# SCH_StorageGuard.net
KiCad netlist of a schematic drawn in EasyEDA
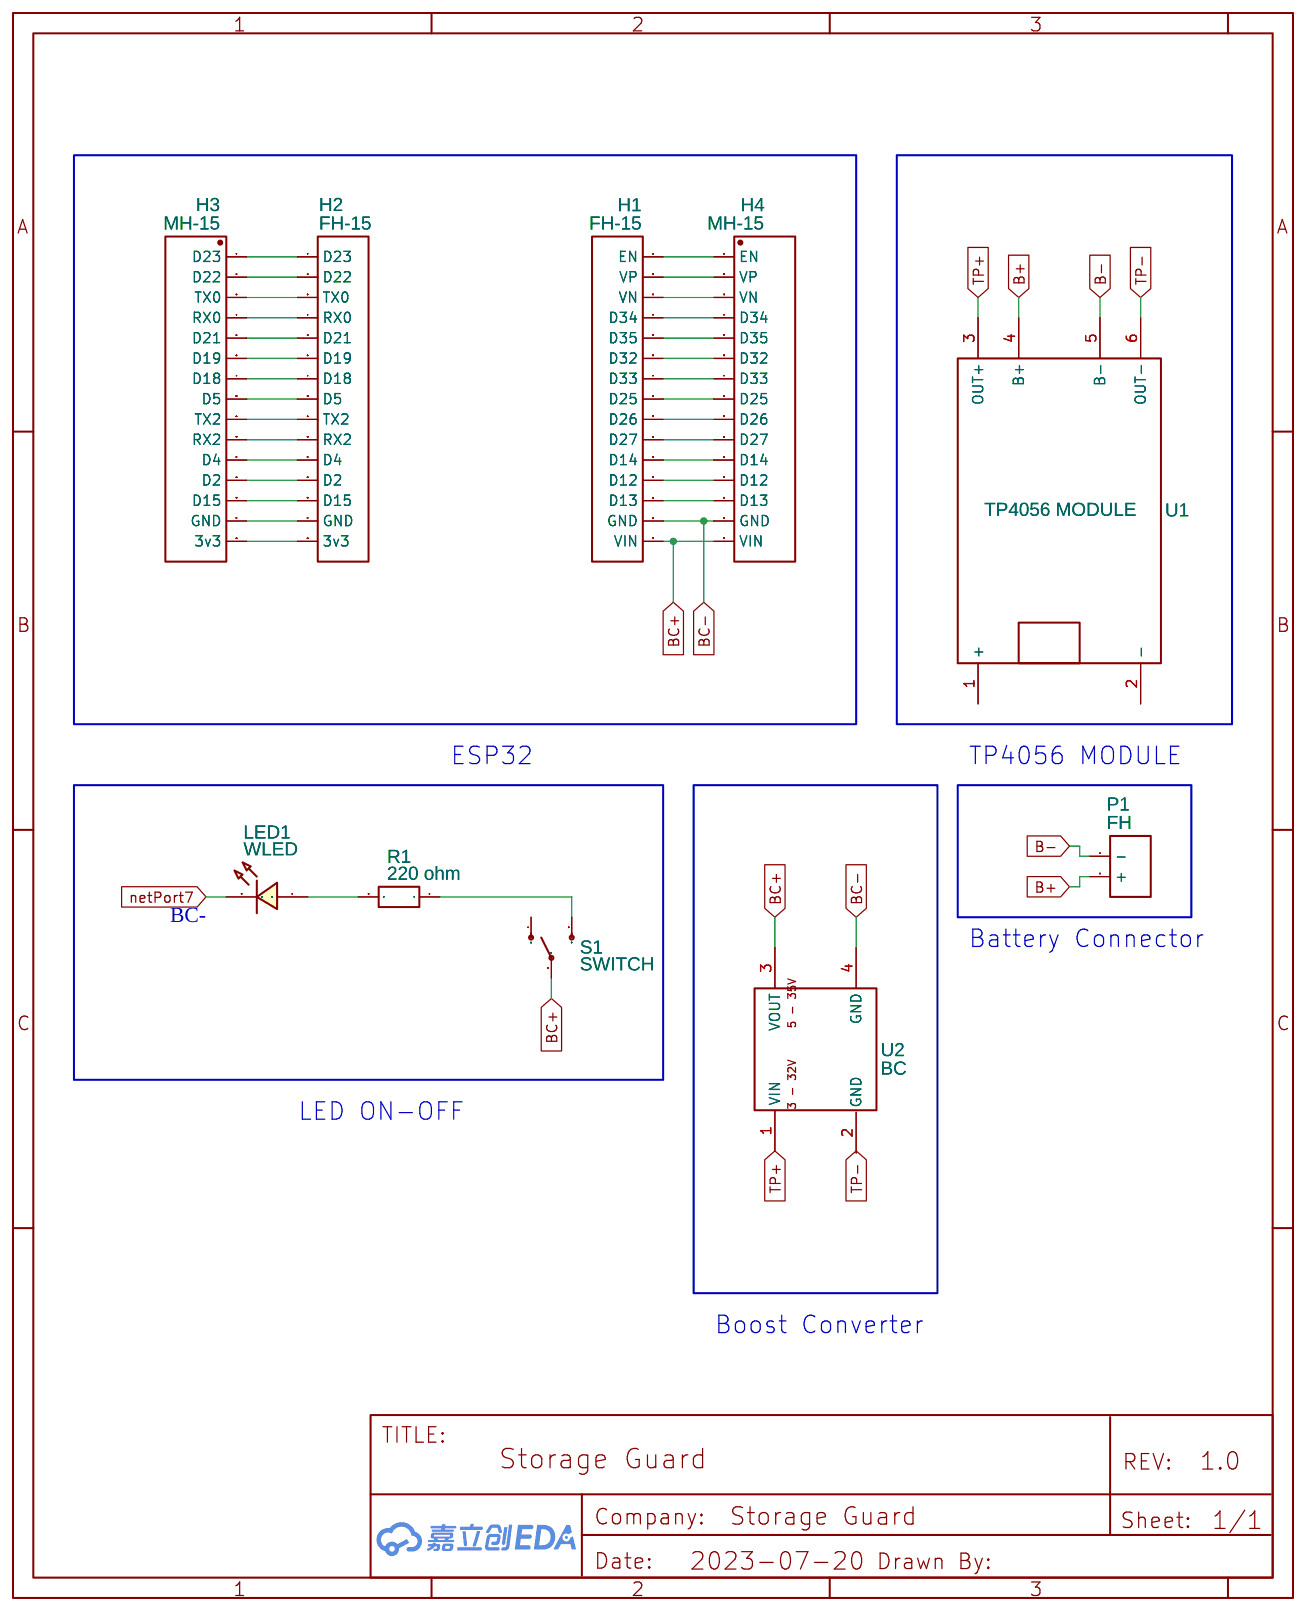
[diagram p0: schematic sheet]

(export (version "E")
  (design (tool "Eeschema 10.0.6"))
  (components
    (comp (ref "H1")
      (value "FH-15")
      (fields
        (field (name "BOM_Manufacturer Part") "B-2200S15P-A120")
        (field (name "BOM_Supplier Part") "C124408")
      )
      (libsource (lib "") (part "Header-Female-2.54_1x15"))
    )
    (comp (ref "H2")
      (value "FH-15")
      (fields
        (field (name "BOM_Manufacturer Part") "B-2200S15P-A120")
        (field (name "BOM_Supplier Part") "C124408")
      )
      (libsource (lib "") (part "Header-Female-2.54_1x15_1"))
    )
    (comp (ref "H3")
      (value "MH-15")
      (fields
        (field (name "BOM_Manufacturer Part") "B-2100S15P-A110")
        (field (name "BOM_Supplier Part") "C124373")
      )
      (libsource (lib "") (part "Header-Male-2.54_1x15"))
    )
    (comp (ref "H4")
      (value "MH-15")
      (fields
        (field (name "BOM_Manufacturer Part") "B-2100S15P-A110")
        (field (name "BOM_Supplier Part") "C124373")
      )
      (libsource (lib "") (part "Header-Male-2.54_1x15_1"))
    )
    (comp (ref "LED1") (value "WLED") (libsource (lib "") (part "LED-TH-5mm_B")))
    (comp (ref "P1")
      (value "FH")
      (fields (field (name "BOM_Manufacturer Part") "2.54-1*2P母") (field (name "BOM_Supplier Part") "C49661"))
      (libsource (lib "") (part "Header-Female-2.54_1x2"))
    )
    (comp (ref "R1")
      (value "220 ohm")
      (fields
        (field (name "BOM_Manufacturer Part") "Resistor_THT:R_Axial_DIN0309_L9.0mm_D3.2mm_P2.54mm_Vertical")
        (field (name "BOM_Supplier Part") "C9900016274")
      )
      (libsource (lib "") (part "RESISTOR_THT{colon}R_AXIAL_DIN0309_L9.0MM_D3.2MM_P2.54MM_VERTICAL"))
    )
    (comp (ref "S1") (value "SWITCH") (libsource (lib "") (part "SWITCH-SPDT-8.5mm")))
    (comp (ref "U1") (value "TP4056 MODULE") (libsource (lib "") (part "TP4056 MODULE")))
    (comp (ref "U2") (value "BC") (libsource (lib "") (part "STEP-UP XL6009E1")))
  )
  (nets
    (net (code "1") (name "B+") (class "Default")
      (node (ref "P1") (pin "2") (pinfunction "+_2") (pintype "input"))
      (node (ref "U1") (pin "4") (pinfunction "B+_4") (pintype "unspecified"))
    )
    (net (code "2") (name "B-") (class "Default")
      (node (ref "P1") (pin "1") (pinfunction "-_1") (pintype "input"))
      (node (ref "U1") (pin "5") (pinfunction "B-_5") (pintype "unspecified"))
    )
    (net (code "3") (name "BC+") (class "Default")
      (node (ref "H1") (pin "15") (pinfunction "VIN_15") (pintype "unspecified"))
      (node (ref "H4") (pin "15") (pinfunction "VIN_15") (pintype "unspecified"))
      (node (ref "S1") (pin "2") (pinfunction "P_2") (pintype "unspecified"))
      (node (ref "U2") (pin "3") (pinfunction "VOUT_3") (pintype "output"))
    )
    (net (code "4") (name "BC-") (class "Default")
      (node (ref "H1") (pin "14") (pinfunction "GND_14") (pintype "unspecified"))
      (node (ref "H4") (pin "14") (pinfunction "GND_14") (pintype "unspecified"))
      (node (ref "U2") (pin "4") (pinfunction "GND_4") (pintype "output"))
    )
    (net (code "5") (name "Net-(H1-D12)") (class "Default")
      (node (ref "H1") (pin "12") (pinfunction "D12_12") (pintype "unspecified"))
      (node (ref "H4") (pin "12") (pinfunction "D12_12") (pintype "unspecified"))
    )
    (net (code "6") (name "Net-(H1-D13)") (class "Default")
      (node (ref "H1") (pin "13") (pinfunction "D13_13") (pintype "unspecified"))
      (node (ref "H4") (pin "13") (pinfunction "D13_13") (pintype "unspecified"))
    )
    (net (code "7") (name "Net-(H1-D14)") (class "Default")
      (node (ref "H1") (pin "11") (pinfunction "D14_11") (pintype "unspecified"))
      (node (ref "H4") (pin "11") (pinfunction "D14_11") (pintype "unspecified"))
    )
    (net (code "8") (name "Net-(H1-D25)") (class "Default")
      (node (ref "H1") (pin "8") (pinfunction "D25_8") (pintype "unspecified"))
      (node (ref "H4") (pin "8") (pinfunction "D25_8") (pintype "unspecified"))
    )
    (net (code "9") (name "Net-(H1-D26)") (class "Default")
      (node (ref "H1") (pin "9") (pinfunction "D26_9") (pintype "unspecified"))
      (node (ref "H4") (pin "9") (pinfunction "D26_9") (pintype "unspecified"))
    )
    (net (code "10") (name "Net-(H1-D27)") (class "Default")
      (node (ref "H1") (pin "10") (pinfunction "D27_10") (pintype "unspecified"))
      (node (ref "H4") (pin "10") (pinfunction "D27_10") (pintype "unspecified"))
    )
    (net (code "11") (name "Net-(H1-D32)") (class "Default")
      (node (ref "H1") (pin "6") (pinfunction "D32_6") (pintype "unspecified"))
      (node (ref "H4") (pin "6") (pinfunction "D32_6") (pintype "unspecified"))
    )
    (net (code "12") (name "Net-(H1-D33)") (class "Default")
      (node (ref "H1") (pin "7") (pinfunction "D33_7") (pintype "unspecified"))
      (node (ref "H4") (pin "7") (pinfunction "D33_7") (pintype "unspecified"))
    )
    (net (code "13") (name "Net-(H1-D34)") (class "Default")
      (node (ref "H1") (pin "4") (pinfunction "D34_4") (pintype "unspecified"))
      (node (ref "H4") (pin "4") (pinfunction "D34_4") (pintype "unspecified"))
    )
    (net (code "14") (name "Net-(H1-D35)") (class "Default")
      (node (ref "H1") (pin "5") (pinfunction "D35_5") (pintype "unspecified"))
      (node (ref "H4") (pin "5") (pinfunction "D35_5") (pintype "unspecified"))
    )
    (net (code "15") (name "Net-(H1-EN)") (class "Default")
      (node (ref "H1") (pin "1") (pinfunction "EN_1") (pintype "unspecified"))
      (node (ref "H4") (pin "1") (pinfunction "EN_1") (pintype "unspecified"))
    )
    (net (code "16") (name "Net-(H1-VN)") (class "Default")
      (node (ref "H1") (pin "3") (pinfunction "VN_3") (pintype "unspecified"))
      (node (ref "H4") (pin "3") (pinfunction "VN_3") (pintype "unspecified"))
    )
    (net (code "17") (name "Net-(H1-VP)") (class "Default")
      (node (ref "H1") (pin "2") (pinfunction "VP_2") (pintype "unspecified"))
      (node (ref "H4") (pin "2") (pinfunction "VP_2") (pintype "unspecified"))
    )
    (net (code "18") (name "Net-(H2-3v3)") (class "Default")
      (node (ref "H2") (pin "15") (pinfunction "3v3_15") (pintype "unspecified"))
      (node (ref "H3") (pin "15") (pinfunction "3v3_15") (pintype "unspecified"))
    )
    (net (code "19") (name "Net-(H2-D2)") (class "Default")
      (node (ref "H2") (pin "12") (pinfunction "D2_12") (pintype "unspecified"))
      (node (ref "H3") (pin "12") (pinfunction "D2_12") (pintype "unspecified"))
    )
    (net (code "20") (name "Net-(H2-D4)") (class "Default")
      (node (ref "H2") (pin "11") (pinfunction "D4_11") (pintype "unspecified"))
      (node (ref "H3") (pin "11") (pinfunction "D4_11") (pintype "unspecified"))
    )
    (net (code "21") (name "Net-(H2-D5)") (class "Default")
      (node (ref "H2") (pin "8") (pinfunction "D5_8") (pintype "unspecified"))
      (node (ref "H3") (pin "8") (pinfunction "D5_8") (pintype "unspecified"))
    )
    (net (code "22") (name "Net-(H2-D15)") (class "Default")
      (node (ref "H2") (pin "13") (pinfunction "D15_13") (pintype "unspecified"))
      (node (ref "H3") (pin "13") (pinfunction "D15_13") (pintype "unspecified"))
    )
    (net (code "23") (name "Net-(H2-D18)") (class "Default")
      (node (ref "H2") (pin "7") (pinfunction "D18_7") (pintype "unspecified"))
      (node (ref "H3") (pin "7") (pinfunction "D18_7") (pintype "unspecified"))
    )
    (net (code "24") (name "Net-(H2-D19)") (class "Default")
      (node (ref "H2") (pin "6") (pinfunction "D19_6") (pintype "unspecified"))
      (node (ref "H3") (pin "6") (pinfunction "D19_6") (pintype "unspecified"))
    )
    (net (code "25") (name "Net-(H2-D21)") (class "Default")
      (node (ref "H2") (pin "5") (pinfunction "D21_5") (pintype "unspecified"))
      (node (ref "H3") (pin "5") (pinfunction "D21_5") (pintype "unspecified"))
    )
    (net (code "26") (name "Net-(H2-D22)") (class "Default")
      (node (ref "H2") (pin "2") (pinfunction "D22_2") (pintype "unspecified"))
      (node (ref "H3") (pin "2") (pinfunction "D22_2") (pintype "unspecified"))
    )
    (net (code "27") (name "Net-(H2-D23)") (class "Default")
      (node (ref "H2") (pin "1") (pinfunction "D23_1") (pintype "unspecified"))
      (node (ref "H3") (pin "1") (pinfunction "D23_1") (pintype "unspecified"))
    )
    (net (code "28") (name "Net-(H2-GND)") (class "Default")
      (node (ref "H2") (pin "14") (pinfunction "GND_14") (pintype "unspecified"))
      (node (ref "H3") (pin "14") (pinfunction "GND_14") (pintype "unspecified"))
    )
    (net (code "29") (name "Net-(H2-RX0)") (class "Default")
      (node (ref "H2") (pin "4") (pinfunction "RX0_4") (pintype "unspecified"))
      (node (ref "H3") (pin "4") (pinfunction "RX0_4") (pintype "unspecified"))
    )
    (net (code "30") (name "Net-(H2-RX2)") (class "Default")
      (node (ref "H2") (pin "10") (pinfunction "RX2_10") (pintype "unspecified"))
      (node (ref "H3") (pin "10") (pinfunction "RX2_10") (pintype "unspecified"))
    )
    (net (code "31") (name "Net-(H2-TX0)") (class "Default")
      (node (ref "H2") (pin "3") (pinfunction "TX0_3") (pintype "unspecified"))
      (node (ref "H3") (pin "3") (pinfunction "TX0_3") (pintype "unspecified"))
    )
    (net (code "32") (name "Net-(H2-TX2)") (class "Default")
      (node (ref "H2") (pin "9") (pinfunction "TX2_9") (pintype "unspecified"))
      (node (ref "H3") (pin "9") (pinfunction "TX2_9") (pintype "unspecified"))
    )
    (net (code "33") (name "Net-(LED1-Pad1)") (class "Default")
      (node (ref "LED1") (pin "1") (pinfunction "1_1") (pintype "unspecified"))
      (node (ref "R1") (pin "2") (pinfunction "2_2") (pintype "unspecified"))
    )
    (net (code "34") (name "Net-(S1-S)") (class "Default")
      (node (ref "R1") (pin "1") (pinfunction "1_1") (pintype "unspecified"))
      (node (ref "S1") (pin "3") (pinfunction "S_3") (pintype "unspecified"))
    )
    (net (code "35") (name "TP+") (class "Default")
      (node (ref "U1") (pin "3") (pinfunction "OUT+_3") (pintype "unspecified"))
      (node (ref "U2") (pin "1") (pinfunction "VIN_1") (pintype "passive"))
    )
    (net (code "36") (name "TP-") (class "Default")
      (node (ref "U1") (pin "6") (pinfunction "OUT-_6") (pintype "unspecified"))
      (node (ref "U2") (pin "2") (pinfunction "GND_2") (pintype "passive"))
    )
    (net (code "37") (name "netPort7") (class "Default")
      (node (ref "LED1") (pin "2") (pinfunction "2_2") (pintype "unspecified"))
    )
    (net (code "38") (name "unconnected-(S1-O-Pad1)") (class "Default")
      (node (ref "S1") (pin "1") (pinfunction "O_1") (pintype "unspecified"))
    )
    (net (code "39") (name "unconnected-(U1-+-Pad1)") (class "Default")
      (node (ref "U1") (pin "1") (pinfunction "+_1") (pintype "unspecified"))
    )
    (net (code "40") (name "unconnected-(U1---Pad2)") (class "Default")
      (node (ref "U1") (pin "2") (pinfunction "-_2") (pintype "unspecified"))
    )
  )
)
